# Power.net
KiCad netlist of a schematic drawn in Altium Designer
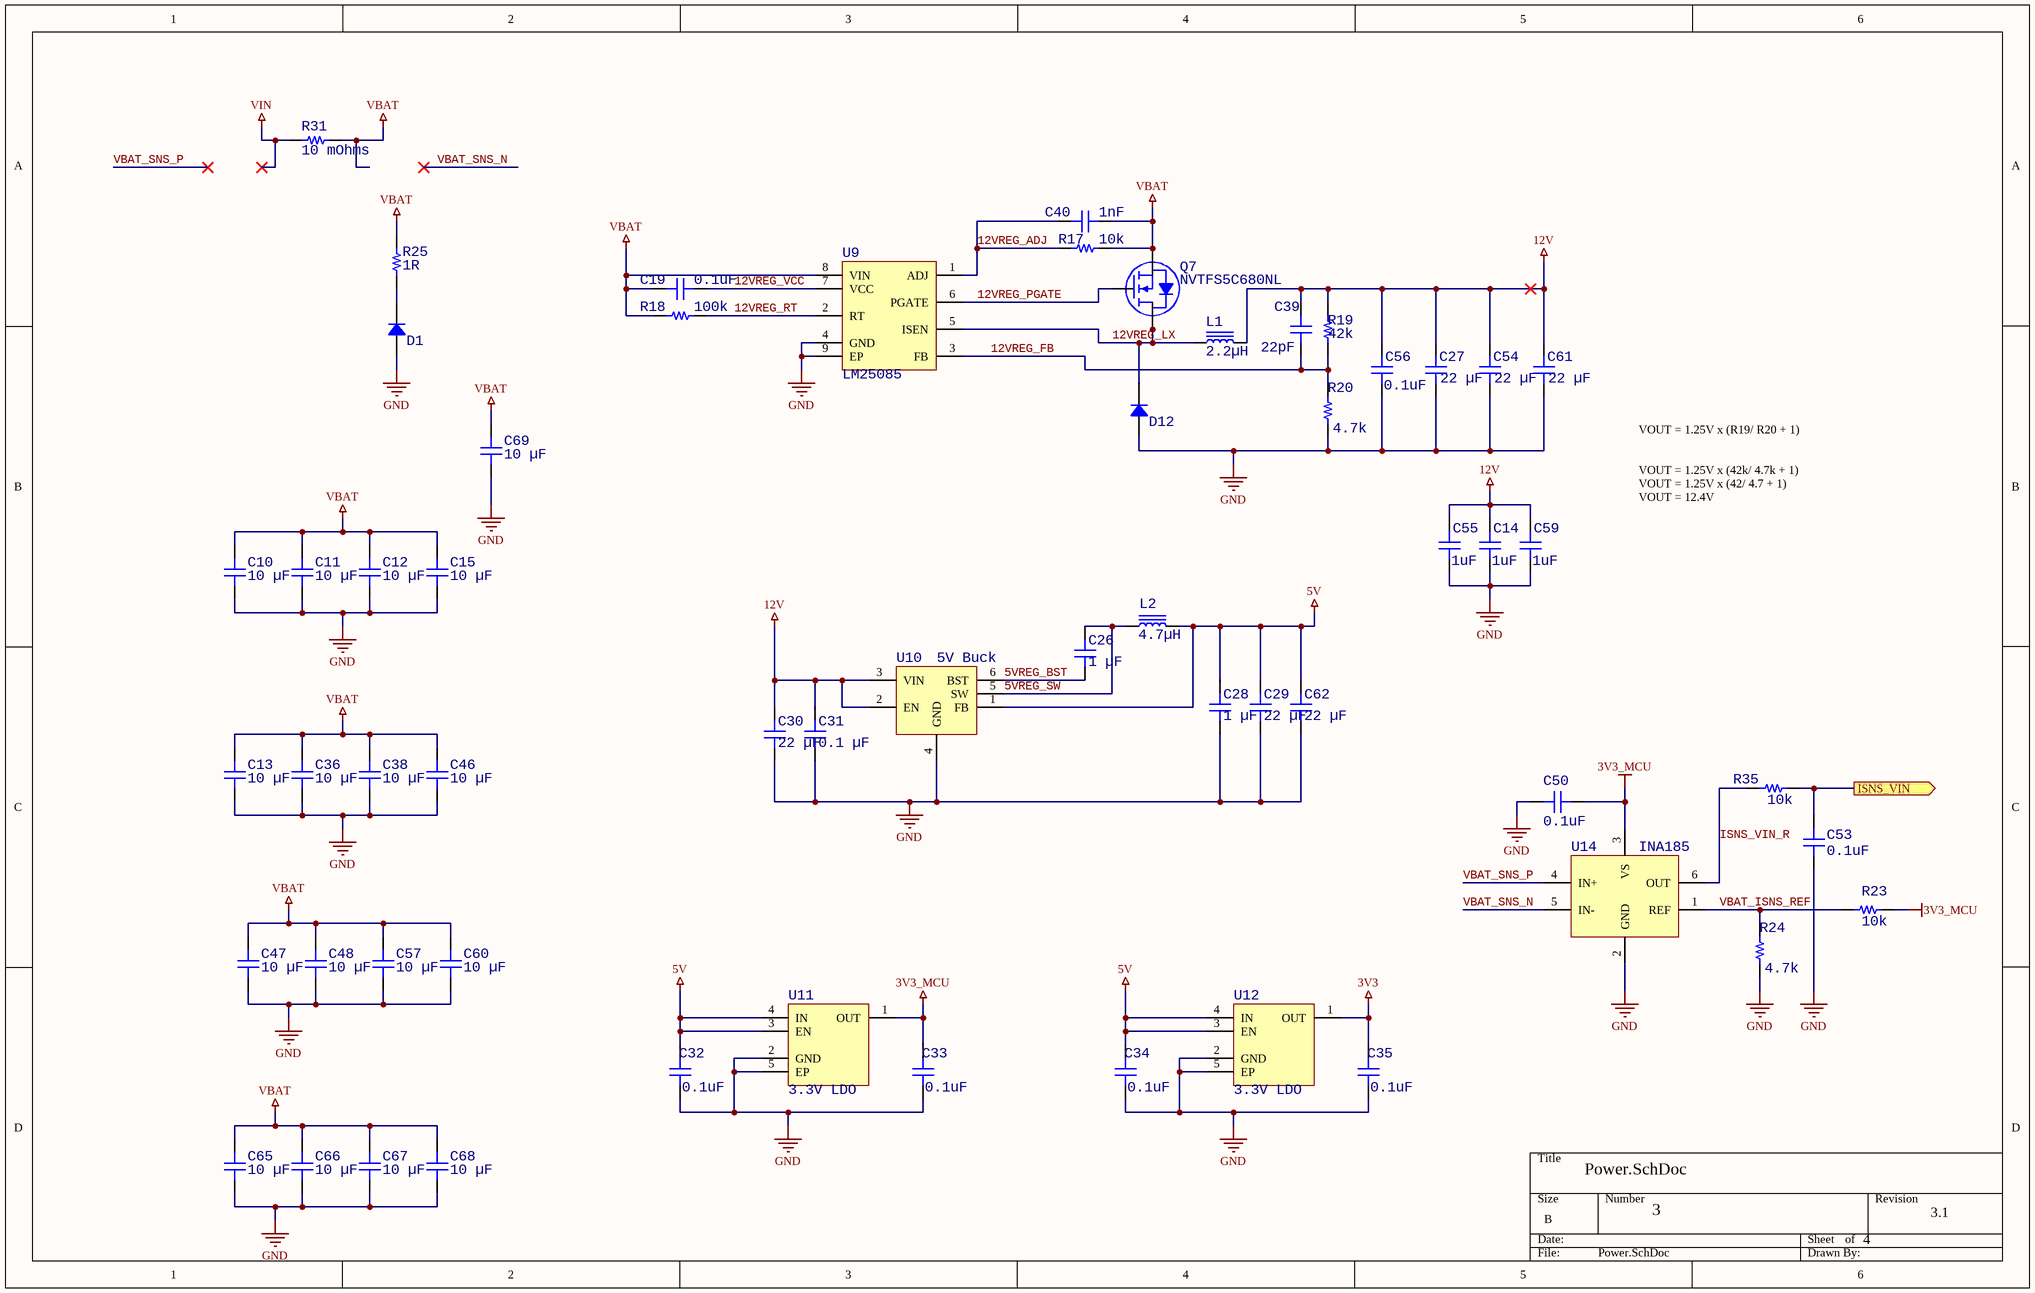
[diagram p0: Power.SchDoc]

(export (version "E")
  (design (tool "Eeschema 10.0.6"))
  (components
    (comp (ref "C10")
      (value "10 µF")
      (footprint "CAP 1206_3216 - 0.8MM")
      (description "CAP CER 10UF 25V X6S 1206")
      (fields
        (field (name "PART NUMBER") "CL31X106KAHNNNE")
        (field (name "MANUFACTURER") "Samsung Electro-Mechanics")
      )
      (libsource (lib "Celestial Altium Library - altium_library") (part "Capacitor"))
    )
    (comp (ref "C11")
      (value "10 µF")
      (footprint "CAP 1206_3216 - 0.8MM")
      (description "CAP CER 10UF 25V X6S 1206")
      (fields
        (field (name "PART NUMBER") "CL31X106KAHNNNE")
        (field (name "MANUFACTURER") "Samsung Electro-Mechanics")
      )
      (libsource (lib "Celestial Altium Library - altium_library") (part "Capacitor"))
    )
    (comp (ref "C12")
      (value "10 µF")
      (footprint "CAP 1206_3216 - 0.8MM")
      (description "CAP CER 10UF 25V X6S 1206")
      (fields
        (field (name "PART NUMBER") "CL31X106KAHNNNE")
        (field (name "MANUFACTURER") "Samsung Electro-Mechanics")
      )
      (libsource (lib "Celestial Altium Library - altium_library") (part "Capacitor"))
    )
    (comp (ref "C13")
      (value "10 µF")
      (footprint "CAP 1206_3216 - 0.8MM")
      (description "CAP CER 10UF 25V X6S 1206")
      (fields
        (field (name "PART NUMBER") "CL31X106KAHNNNE")
        (field (name "MANUFACTURER") "Samsung Electro-Mechanics")
      )
      (libsource (lib "Celestial Altium Library - altium_library") (part "Capacitor"))
    )
    (comp (ref "C14")
      (value "1uF")
      (footprint "CAP_0402")
      (description "CAP CER 402")
      (libsource (lib "IC") (part "CAP_0402"))
    )
    (comp (ref "C15")
      (value "10 µF")
      (footprint "CAP 1206_3216 - 0.8MM")
      (description "CAP CER 10UF 25V X6S 1206")
      (fields
        (field (name "PART NUMBER") "CL31X106KAHNNNE")
        (field (name "MANUFACTURER") "Samsung Electro-Mechanics")
      )
      (libsource (lib "Celestial Altium Library - altium_library") (part "Capacitor"))
    )
    (comp (ref "C19")
      (value "0.1uF")
      (footprint "CAP_0402")
      (description "CAP CER 402")
      (libsource (lib "IC") (part "CAP_0402"))
    )
    (comp (ref "C26")
      (value "1 µF")
      (footprint "CAP 0402_1005")
      (description "CAP CER 0.1UF 16V X7R 0402")
      (fields (field (name "PART NUMBER") "C0402C104K4RACAUTO") (field (name "MANUFACTURER") "KEMET"))
      (libsource (lib "Celestial Altium Library - altium_library") (part "Capacitor"))
    )
    (comp (ref "C27")
      (value "22 µF")
      (footprint "CAP 0805_2012")
      (description "CAP CER 22UF 16V X6S 0805")
      (fields (field (name "PART NUMBER") "KGM21AS61C226MU") (field (name "MANUFACTURER") "KYOCERA AVX"))
      (libsource (lib "Celestial Altium Library - altium_library") (part "Capacitor"))
    )
    (comp (ref "C28")
      (value "1 µF")
      (footprint "CAP 0402_1005")
      (description "CAP CER 0.1UF 16V X7R 0402")
      (fields (field (name "PART NUMBER") "C0402C104K4RACAUTO") (field (name "MANUFACTURER") "KEMET"))
      (libsource (lib "Celestial Altium Library - altium_library") (part "Capacitor"))
    )
    (comp (ref "C29")
      (value "22 µF")
      (footprint "CAP 0603_1608")
      (description "CAP CER 47UF 6.3V X5R 0603")
      (fields
        (field (name "PART NUMBER") "C0603B476M007T")
        (field (name "MANUFACTURER") "Holy Stone Enterprise Co., Ltd.")
      )
      (libsource (lib "Celestial Altium Library - altium_library") (part "Capacitor"))
    )
    (comp (ref "C30")
      (value "22 µF")
      (footprint "CAP 0603_1608")
      (description "CAP CER 47UF 6.3V X5R 0603")
      (fields
        (field (name "PART NUMBER") "C0603B476M007T")
        (field (name "MANUFACTURER") "Holy Stone Enterprise Co., Ltd.")
      )
      (libsource (lib "Celestial Altium Library - altium_library") (part "Capacitor"))
    )
    (comp (ref "C31")
      (value "0.1 µF")
      (footprint "CAP 0402_1005")
      (description "CAP CER 0.1UF 16V X7R 0402")
      (fields (field (name "PART NUMBER") "C0402C104K4RACAUTO") (field (name "MANUFACTURER") "KEMET"))
      (libsource (lib "Celestial Altium Library - altium_library") (part "Capacitor"))
    )
    (comp (ref "C32")
      (value "0.1uF")
      (footprint "CAP_0402")
      (description "CAP CER 402")
      (libsource (lib "IC") (part "CAP_0402"))
    )
    (comp (ref "C33")
      (value "0.1uF")
      (footprint "CAP_0402")
      (description "CAP CER 402")
      (libsource (lib "IC") (part "CAP_0402"))
    )
    (comp (ref "C34")
      (value "0.1uF")
      (footprint "CAP_0402")
      (description "CAP CER 402")
      (libsource (lib "IC") (part "CAP_0402"))
    )
    (comp (ref "C35")
      (value "0.1uF")
      (footprint "CAP_0402")
      (description "CAP CER 402")
      (libsource (lib "IC") (part "CAP_0402"))
    )
    (comp (ref "C36")
      (value "10 µF")
      (footprint "CAP 1206_3216 - 0.8MM")
      (description "CAP CER 10UF 25V X6S 1206")
      (fields
        (field (name "PART NUMBER") "CL31X106KAHNNNE")
        (field (name "MANUFACTURER") "Samsung Electro-Mechanics")
      )
      (libsource (lib "Celestial Altium Library - altium_library") (part "Capacitor"))
    )
    (comp (ref "C38")
      (value "10 µF")
      (footprint "CAP 1206_3216 - 0.8MM")
      (description "CAP CER 10UF 25V X6S 1206")
      (fields
        (field (name "PART NUMBER") "CL31X106KAHNNNE")
        (field (name "MANUFACTURER") "Samsung Electro-Mechanics")
      )
      (libsource (lib "Celestial Altium Library - altium_library") (part "Capacitor"))
    )
    (comp (ref "C39")
      (value "22pF")
      (footprint "CAP_0402")
      (description "CAP CER 402")
      (libsource (lib "IC") (part "CAP_0402"))
    )
    (comp (ref "C40")
      (value "1nF")
      (footprint "CAP_0402")
      (description "CAP CER 402")
      (libsource (lib "IC") (part "CAP_0402"))
    )
    (comp (ref "C46")
      (value "10 µF")
      (footprint "CAP 1206_3216 - 0.8MM")
      (description "CAP CER 10UF 25V X6S 1206")
      (fields
        (field (name "PART NUMBER") "CL31X106KAHNNNE")
        (field (name "MANUFACTURER") "Samsung Electro-Mechanics")
      )
      (libsource (lib "Celestial Altium Library - altium_library") (part "Capacitor"))
    )
    (comp (ref "C47")
      (value "10 µF")
      (footprint "CAP 1206_3216 - 0.8MM")
      (description "CAP CER 10UF 25V X6S 1206")
      (fields
        (field (name "PART NUMBER") "CL31X106KAHNNNE")
        (field (name "MANUFACTURER") "Samsung Electro-Mechanics")
      )
      (libsource (lib "Celestial Altium Library - altium_library") (part "Capacitor"))
    )
    (comp (ref "C48")
      (value "10 µF")
      (footprint "CAP 1206_3216 - 0.8MM")
      (description "CAP CER 10UF 25V X6S 1206")
      (fields
        (field (name "PART NUMBER") "CL31X106KAHNNNE")
        (field (name "MANUFACTURER") "Samsung Electro-Mechanics")
      )
      (libsource (lib "Celestial Altium Library - altium_library") (part "Capacitor"))
    )
    (comp (ref "C50")
      (value "0.1uF")
      (footprint "CAP_0402")
      (description "CAP CER 402")
      (libsource (lib "IC") (part "CAP_0402"))
    )
    (comp (ref "C53")
      (value "0.1uF")
      (footprint "CAP_0402")
      (description "CAP CER 402")
      (libsource (lib "IC") (part "CAP_0402"))
    )
    (comp (ref "C54")
      (value "22 µF")
      (footprint "CAP 0805_2012")
      (description "CAP CER 22UF 16V X6S 0805")
      (fields (field (name "PART NUMBER") "KGM21AS61C226MU") (field (name "MANUFACTURER") "KYOCERA AVX"))
      (libsource (lib "Celestial Altium Library - altium_library") (part "Capacitor"))
    )
    (comp (ref "C55")
      (value "1uF")
      (footprint "CAP_0402")
      (description "CAP CER 402")
      (libsource (lib "IC") (part "CAP_0402"))
    )
    (comp (ref "C56")
      (value "0.1uF")
      (footprint "CAP_0402")
      (description "CAP CER 402")
      (libsource (lib "IC") (part "CAP_0402"))
    )
    (comp (ref "C57")
      (value "10 µF")
      (footprint "CAP 1206_3216 - 0.8MM")
      (description "CAP CER 10UF 25V X6S 1206")
      (fields
        (field (name "PART NUMBER") "CL31X106KAHNNNE")
        (field (name "MANUFACTURER") "Samsung Electro-Mechanics")
      )
      (libsource (lib "Celestial Altium Library - altium_library") (part "Capacitor"))
    )
    (comp (ref "C59")
      (value "1uF")
      (footprint "CAP_0402")
      (description "CAP CER 402")
      (libsource (lib "IC") (part "CAP_0402"))
    )
    (comp (ref "C60")
      (value "10 µF")
      (footprint "CAP 1206_3216 - 0.8MM")
      (description "CAP CER 10UF 25V X6S 1206")
      (fields
        (field (name "PART NUMBER") "CL31X106KAHNNNE")
        (field (name "MANUFACTURER") "Samsung Electro-Mechanics")
      )
      (libsource (lib "Celestial Altium Library - altium_library") (part "Capacitor"))
    )
    (comp (ref "C61")
      (value "22 µF")
      (footprint "CAP 0805_2012")
      (description "CAP CER 22UF 16V X6S 0805")
      (fields (field (name "PART NUMBER") "KGM21AS61C226MU") (field (name "MANUFACTURER") "KYOCERA AVX"))
      (libsource (lib "Celestial Altium Library - altium_library") (part "Capacitor"))
    )
    (comp (ref "C62")
      (value "22 µF")
      (footprint "CAP 0603_1608")
      (description "CAP CER 47UF 6.3V X5R 0603")
      (fields
        (field (name "PART NUMBER") "C0603B476M007T")
        (field (name "MANUFACTURER") "Holy Stone Enterprise Co., Ltd.")
      )
      (libsource (lib "Celestial Altium Library - altium_library") (part "Capacitor"))
    )
    (comp (ref "C65")
      (value "10 µF")
      (footprint "CAP 1206_3216 - 0.8MM")
      (description "CAP CER 10UF 25V X6S 1206")
      (fields
        (field (name "PART NUMBER") "CL31X106KAHNNNE")
        (field (name "MANUFACTURER") "Samsung Electro-Mechanics")
      )
      (libsource (lib "Celestial Altium Library - altium_library") (part "Capacitor"))
    )
    (comp (ref "C66")
      (value "10 µF")
      (footprint "CAP 1206_3216 - 0.8MM")
      (description "CAP CER 10UF 25V X6S 1206")
      (fields
        (field (name "PART NUMBER") "CL31X106KAHNNNE")
        (field (name "MANUFACTURER") "Samsung Electro-Mechanics")
      )
      (libsource (lib "Celestial Altium Library - altium_library") (part "Capacitor"))
    )
    (comp (ref "C67")
      (value "10 µF")
      (footprint "CAP 1206_3216 - 0.8MM")
      (description "CAP CER 10UF 25V X6S 1206")
      (fields
        (field (name "PART NUMBER") "CL31X106KAHNNNE")
        (field (name "MANUFACTURER") "Samsung Electro-Mechanics")
      )
      (libsource (lib "Celestial Altium Library - altium_library") (part "Capacitor"))
    )
    (comp (ref "C68")
      (value "10 µF")
      (footprint "CAP 1206_3216 - 0.8MM")
      (description "CAP CER 10UF 25V X6S 1206")
      (fields
        (field (name "PART NUMBER") "CL31X106KAHNNNE")
        (field (name "MANUFACTURER") "Samsung Electro-Mechanics")
      )
      (libsource (lib "Celestial Altium Library - altium_library") (part "Capacitor"))
    )
    (comp (ref "C69")
      (value "10 µF")
      (footprint "CAP 1206_3216 - 0.8MM")
      (description "CAP CER 10UF 25V X6S 1206")
      (fields
        (field (name "PART NUMBER") "CL31X106KAHNNNE")
        (field (name "MANUFACTURER") "Samsung Electro-Mechanics")
      )
      (libsource (lib "Celestial Altium Library - altium_library") (part "Capacitor"))
    )
    (comp (ref "D1")
      (value "SE10FGHM3/H")
      (footprint "SMF DO-219AB")
      (description "DIODE GEN PURP 400V 1A DO219AB")
      (fields (field (name "MANUFACTURER") "Vishay Semiconductor Diodes Division"))
      (libsource (lib "Celestial Altium Library - altium_library") (part "Diode"))
    )
    (comp (ref "D12")
      (value "SE10FGHM3/H")
      (footprint "SMF DO-219AB")
      (description "DIODE GEN PURP 400V 1A DO219AB")
      (fields (field (name "MANUFACTURER") "Vishay Semiconductor Diodes Division"))
      (libsource (lib "Celestial Altium Library - altium_library") (part "Diode"))
    )
    (comp (ref "L1")
      (value "2.2µH")
      (footprint "IND 1008_2520")
      (description "FIXED IND 2.2UH 1.5A 90 MOHM SMD")
      (fields (field (name "PART NUMBER") "AIML-1008HC-2R2M-T") (field (name "MANUFACTURER") "Abracon LLC"))
      (libsource (lib "Celestial Altium Library - altium_library") (part "Inductor"))
    )
    (comp (ref "L2")
      (value "4.7µH")
      (footprint "IND 1008_2520")
      (description "FIXED IND 4.7UH 1A 110 MOHM SMD")
      (fields (field (name "PART NUMBER") "MLP2520S4R7ST0S1") (field (name "MANUFACTURER") "TDK Corporation"))
      (libsource (lib "Celestial Altium Library - altium_library") (part "Inductor"))
    )
    (comp (ref "Q7")
      (value "NVTFS5C680NL")
      (footprint "NVTFS015N04CTAG")
      (description "N-FET")
      (libsource (lib "IC") (part "NVTFS5C680NL"))
    )
    (comp (ref "R17")
      (value "10k")
      (footprint "RES_0402")
      (description "RES 0402")
      (libsource (lib "IC") (part "RES_0402"))
    )
    (comp (ref "R18")
      (value "100k")
      (footprint "RES_0402")
      (description "RES 0402")
      (libsource (lib "IC") (part "RES_0402"))
    )
    (comp (ref "R19")
      (value "42k")
      (footprint "RES_0402")
      (description "RES 0402")
      (libsource (lib "IC") (part "RES_0402"))
    )
    (comp (ref "R20")
      (value "4.7k")
      (footprint "RES_0402")
      (description "RES 0402")
      (libsource (lib "IC") (part "RES_0402"))
    )
    (comp (ref "R23")
      (value "10k")
      (footprint "RES_0402")
      (description "RES 0402")
      (libsource (lib "IC") (part "RES_0402"))
    )
    (comp (ref "R24")
      (value "4.7k")
      (footprint "RES_0402")
      (description "RES 0402")
      (libsource (lib "IC") (part "RES_0402"))
    )
    (comp (ref "R25")
      (value "1R")
      (footprint "RES 0603_1608")
      (description "1/16 WATTS PRECISION CHIP 1 KILO")
      (fields (field (name "PART NUMBER") "APC0603B1K00N") (field (name "MANUFACTURER") "Ohmite"))
      (libsource (lib "Celestial Altium Library - altium_library") (part "Resistor"))
    )
    (comp (ref "R31")
      (value "10 mOhms")
      (footprint "RES 1206_3216")
      (description "RES 0.039 OHM 1% 3/4W 1206")
      (fields (field (name "PART NUMBER") "KRL1632E-M-R039-F-T5") (field (name "MANUFACTURER") "Susumu"))
      (libsource (lib "Celestial Altium Library - altium_library") (part "Resistor"))
    )
    (comp (ref "R35")
      (value "10k")
      (footprint "RES_0402")
      (description "RES 0402")
      (libsource (lib "IC") (part "RES_0402"))
    )
    (comp (ref "U9")
      (value "LM25085")
      (footprint "8_WSON_3x3_0.5mm")
      (description "PFET Buck Controller")
      (libsource (lib "IC") (part "LM25085"))
    )
    (comp (ref "U10")
      (value "5V Buck")
      (footprint "TSOT-26-6 - 3.2mm")
      (description "5V fixed step down Buck")
      (libsource (lib "IC") (part "AP63205WU-7"))
    )
    (comp (ref "U11") (value "3.3V LDO") (footprint "XDFN-4") (libsource (lib "IC") (part "TLV74033PDQNR")))
    (comp (ref "U12") (value "3.3V LDO") (footprint "XDFN-4") (libsource (lib "IC") (part "TLV74033PDQNR")))
    (comp (ref "U14")
      (value "INA185")
      (footprint "TI SC70-6 DCK")
      (description "INA185A2")
      (libsource (lib "IC") (part "INA185"))
    )
  )
  (nets
    (net (code "1") (name "/5VREG_BST") (class "Default")
      (node (ref "C26") (pin "1") (pinfunction "1_1") (pintype "passive"))
      (node (ref "U10") (pin "6") (pinfunction "BST_6") (pintype "passive"))
    )
    (net (code "2") (name "/5VREG_SW") (class "Default")
      (node (ref "C26") (pin "2") (pinfunction "2_2") (pintype "passive"))
      (node (ref "L2") (pin "1") (pinfunction "1_1") (pintype "passive"))
      (node (ref "U10") (pin "5") (pinfunction "SW_5") (pintype "passive"))
    )
    (net (code "3") (name "/12VREG_ADJ") (class "Default")
      (node (ref "C40") (pin "1") (pinfunction "1_1") (pintype "passive"))
      (node (ref "R17") (pin "2") (pinfunction "2_2") (pintype "passive"))
      (node (ref "U9") (pin "1") (pinfunction "ADJ_1") (pintype "passive"))
    )
    (net (code "4") (name "/12VREG_FB") (class "Default")
      (node (ref "C39") (pin "1") (pinfunction "1_1") (pintype "passive"))
      (node (ref "R19") (pin "2") (pinfunction "2_2") (pintype "passive"))
      (node (ref "R20") (pin "1") (pinfunction "1_1") (pintype "passive"))
      (node (ref "U9") (pin "3") (pinfunction "FB_3") (pintype "passive"))
    )
    (net (code "5") (name "/12VREG_LX") (class "Default")
      (node (ref "D12") (pin "2") (pinfunction "2_2") (pintype "passive"))
      (node (ref "L1") (pin "1") (pinfunction "1_1") (pintype "passive"))
      (node (ref "Q7") (pin "5") (pinfunction "D_5") (pintype "passive"))
      (node (ref "Q7") (pin "6") (pinfunction "D_6") (pintype "passive"))
      (node (ref "Q7") (pin "7") (pinfunction "D_7") (pintype "passive"))
      (node (ref "Q7") (pin "8") (pinfunction "D_8") (pintype "passive"))
      (node (ref "U9") (pin "5") (pinfunction "ISEN_5") (pintype "passive"))
    )
    (net (code "6") (name "/12VREG_PGATE") (class "Default")
      (node (ref "Q7") (pin "4") (pinfunction "G_4") (pintype "passive"))
      (node (ref "U9") (pin "6") (pinfunction "PGATE_6") (pintype "passive"))
    )
    (net (code "7") (name "/12VREG_RT") (class "Default")
      (node (ref "R18") (pin "1") (pinfunction "1_1") (pintype "passive"))
      (node (ref "U9") (pin "2") (pinfunction "RT_2") (pintype "passive"))
    )
    (net (code "8") (name "/12VREG_VCC") (class "Default")
      (node (ref "C19") (pin "2") (pinfunction "2_2") (pintype "passive"))
      (node (ref "U9") (pin "7") (pinfunction "VCC_7") (pintype "passive"))
    )
    (net (code "9") (name "/ISNS_VIN") (class "Default")
      (node (ref "C53") (pin "1") (pinfunction "1_1") (pintype "passive"))
      (node (ref "R35") (pin "1") (pinfunction "1_1") (pintype "passive"))
    )
    (net (code "10") (name "/ISNS_VIN_R") (class "Default")
      (node (ref "R35") (pin "2") (pinfunction "2_2") (pintype "passive"))
      (node (ref "U14") (pin "6") (pinfunction "OUT_6") (pintype "passive"))
    )
    (net (code "11") (name "/VBAT_ISNS_REF") (class "Default")
      (node (ref "R23") (pin "2") (pinfunction "2_2") (pintype "passive"))
      (node (ref "R24") (pin "1") (pinfunction "1_1") (pintype "passive"))
      (node (ref "U14") (pin "1") (pinfunction "REF_1") (pintype "passive"))
    )
    (net (code "12") (name "/VBAT_SNS_N") (class "Default")
      (node (ref "U14") (pin "5") (pinfunction "IN-_5") (pintype "passive"))
    )
    (net (code "13") (name "/VBAT_SNS_P") (class "Default")
      (node (ref "U14") (pin "4") (pinfunction "IN+_4") (pintype "passive"))
    )
    (net (code "14") (name "3V3") (class "Default")
      (node (ref "C35") (pin "2") (pinfunction "2_2") (pintype "passive"))
      (node (ref "U12") (pin "1") (pinfunction "OUT_1") (pintype "passive"))
    )
    (net (code "15") (name "3V3_MCU") (class "Default")
      (node (ref "C33") (pin "2") (pinfunction "2_2") (pintype "passive"))
      (node (ref "C50") (pin "1") (pinfunction "1_1") (pintype "passive"))
      (node (ref "R23") (pin "1") (pinfunction "1_1") (pintype "passive"))
      (node (ref "U11") (pin "1") (pinfunction "OUT_1") (pintype "passive"))
      (node (ref "U14") (pin "3") (pinfunction "VS_3") (pintype "passive"))
    )
    (net (code "16") (name "5V") (class "Default")
      (node (ref "C28") (pin "2") (pinfunction "2_2") (pintype "passive"))
      (node (ref "C29") (pin "2") (pinfunction "2_2") (pintype "passive"))
      (node (ref "C32") (pin "2") (pinfunction "2_2") (pintype "passive"))
      (node (ref "C34") (pin "2") (pinfunction "2_2") (pintype "passive"))
      (node (ref "C62") (pin "2") (pinfunction "2_2") (pintype "passive"))
      (node (ref "L2") (pin "2") (pinfunction "2_2") (pintype "passive"))
      (node (ref "U10") (pin "1") (pinfunction "FB_1") (pintype "passive"))
      (node (ref "U11") (pin "3") (pinfunction "EN_3") (pintype "passive"))
      (node (ref "U11") (pin "4") (pinfunction "IN_4") (pintype "passive"))
      (node (ref "U12") (pin "3") (pinfunction "EN_3") (pintype "passive"))
      (node (ref "U12") (pin "4") (pinfunction "IN_4") (pintype "passive"))
    )
    (net (code "17") (name "12V") (class "Default")
      (node (ref "C14") (pin "2") (pinfunction "2_2") (pintype "passive"))
      (node (ref "C27") (pin "2") (pinfunction "2_2") (pintype "passive"))
      (node (ref "C30") (pin "2") (pinfunction "2_2") (pintype "passive"))
      (node (ref "C31") (pin "2") (pinfunction "2_2") (pintype "passive"))
      (node (ref "C39") (pin "2") (pinfunction "2_2") (pintype "passive"))
      (node (ref "C54") (pin "2") (pinfunction "2_2") (pintype "passive"))
      (node (ref "C55") (pin "2") (pinfunction "2_2") (pintype "passive"))
      (node (ref "C56") (pin "2") (pinfunction "2_2") (pintype "passive"))
      (node (ref "C59") (pin "2") (pinfunction "2_2") (pintype "passive"))
      (node (ref "C61") (pin "2") (pinfunction "2_2") (pintype "passive"))
      (node (ref "L1") (pin "2") (pinfunction "2_2") (pintype "passive"))
      (node (ref "R19") (pin "1") (pinfunction "1_1") (pintype "passive"))
      (node (ref "U10") (pin "2") (pinfunction "EN_2") (pintype "passive"))
      (node (ref "U10") (pin "3") (pinfunction "VIN_3") (pintype "passive"))
    )
    (net (code "18") (name "GND") (class "Default")
      (node (ref "C10") (pin "1") (pinfunction "1_1") (pintype "passive"))
      (node (ref "C11") (pin "1") (pinfunction "1_1") (pintype "passive"))
      (node (ref "C12") (pin "1") (pinfunction "1_1") (pintype "passive"))
      (node (ref "C13") (pin "1") (pinfunction "1_1") (pintype "passive"))
      (node (ref "C14") (pin "1") (pinfunction "1_1") (pintype "passive"))
      (node (ref "C15") (pin "1") (pinfunction "1_1") (pintype "passive"))
      (node (ref "C27") (pin "1") (pinfunction "1_1") (pintype "passive"))
      (node (ref "C28") (pin "1") (pinfunction "1_1") (pintype "passive"))
      (node (ref "C29") (pin "1") (pinfunction "1_1") (pintype "passive"))
      (node (ref "C30") (pin "1") (pinfunction "1_1") (pintype "passive"))
      (node (ref "C31") (pin "1") (pinfunction "1_1") (pintype "passive"))
      (node (ref "C32") (pin "1") (pinfunction "1_1") (pintype "passive"))
      (node (ref "C33") (pin "1") (pinfunction "1_1") (pintype "passive"))
      (node (ref "C34") (pin "1") (pinfunction "1_1") (pintype "passive"))
      (node (ref "C35") (pin "1") (pinfunction "1_1") (pintype "passive"))
      (node (ref "C36") (pin "1") (pinfunction "1_1") (pintype "passive"))
      (node (ref "C38") (pin "1") (pinfunction "1_1") (pintype "passive"))
      (node (ref "C46") (pin "1") (pinfunction "1_1") (pintype "passive"))
      (node (ref "C47") (pin "1") (pinfunction "1_1") (pintype "passive"))
      (node (ref "C48") (pin "1") (pinfunction "1_1") (pintype "passive"))
      (node (ref "C50") (pin "2") (pinfunction "2_2") (pintype "passive"))
      (node (ref "C53") (pin "2") (pinfunction "2_2") (pintype "passive"))
      (node (ref "C54") (pin "1") (pinfunction "1_1") (pintype "passive"))
      (node (ref "C55") (pin "1") (pinfunction "1_1") (pintype "passive"))
      (node (ref "C56") (pin "1") (pinfunction "1_1") (pintype "passive"))
      (node (ref "C57") (pin "1") (pinfunction "1_1") (pintype "passive"))
      (node (ref "C59") (pin "1") (pinfunction "1_1") (pintype "passive"))
      (node (ref "C60") (pin "1") (pinfunction "1_1") (pintype "passive"))
      (node (ref "C61") (pin "1") (pinfunction "1_1") (pintype "passive"))
      (node (ref "C62") (pin "1") (pinfunction "1_1") (pintype "passive"))
      (node (ref "C65") (pin "1") (pinfunction "1_1") (pintype "passive"))
      (node (ref "C66") (pin "1") (pinfunction "1_1") (pintype "passive"))
      (node (ref "C67") (pin "1") (pinfunction "1_1") (pintype "passive"))
      (node (ref "C68") (pin "1") (pinfunction "1_1") (pintype "passive"))
      (node (ref "C69") (pin "1") (pinfunction "1_1") (pintype "passive"))
      (node (ref "D1") (pin "1") (pinfunction "1_1") (pintype "passive"))
      (node (ref "D12") (pin "1") (pinfunction "1_1") (pintype "passive"))
      (node (ref "R20") (pin "2") (pinfunction "2_2") (pintype "passive"))
      (node (ref "R24") (pin "2") (pinfunction "2_2") (pintype "passive"))
      (node (ref "U10") (pin "4") (pinfunction "GND_4") (pintype "passive"))
      (node (ref "U11") (pin "2") (pinfunction "GND_2") (pintype "passive"))
      (node (ref "U11") (pin "5") (pinfunction "EP_5") (pintype "passive"))
      (node (ref "U12") (pin "2") (pinfunction "GND_2") (pintype "passive"))
      (node (ref "U12") (pin "5") (pinfunction "EP_5") (pintype "passive"))
      (node (ref "U14") (pin "2") (pinfunction "GND_2") (pintype "passive"))
      (node (ref "U9") (pin "4") (pinfunction "GND_4") (pintype "passive"))
      (node (ref "U9") (pin "9") (pinfunction "EP_9") (pintype "passive"))
    )
    (net (code "19") (name "Net-(D1-Pad2)") (class "Default")
      (node (ref "D1") (pin "2") (pinfunction "2_2") (pintype "passive"))
      (node (ref "R25") (pin "1") (pinfunction "1_1") (pintype "passive"))
    )
    (net (code "20") (name "VBAT") (class "Default")
      (node (ref "C10") (pin "2") (pinfunction "2_2") (pintype "passive"))
      (node (ref "C11") (pin "2") (pinfunction "2_2") (pintype "passive"))
      (node (ref "C12") (pin "2") (pinfunction "2_2") (pintype "passive"))
      (node (ref "C13") (pin "2") (pinfunction "2_2") (pintype "passive"))
      (node (ref "C15") (pin "2") (pinfunction "2_2") (pintype "passive"))
      (node (ref "C19") (pin "1") (pinfunction "1_1") (pintype "passive"))
      (node (ref "C36") (pin "2") (pinfunction "2_2") (pintype "passive"))
      (node (ref "C38") (pin "2") (pinfunction "2_2") (pintype "passive"))
      (node (ref "C40") (pin "2") (pinfunction "2_2") (pintype "passive"))
      (node (ref "C46") (pin "2") (pinfunction "2_2") (pintype "passive"))
      (node (ref "C47") (pin "2") (pinfunction "2_2") (pintype "passive"))
      (node (ref "C48") (pin "2") (pinfunction "2_2") (pintype "passive"))
      (node (ref "C57") (pin "2") (pinfunction "2_2") (pintype "passive"))
      (node (ref "C60") (pin "2") (pinfunction "2_2") (pintype "passive"))
      (node (ref "C65") (pin "2") (pinfunction "2_2") (pintype "passive"))
      (node (ref "C66") (pin "2") (pinfunction "2_2") (pintype "passive"))
      (node (ref "C67") (pin "2") (pinfunction "2_2") (pintype "passive"))
      (node (ref "C68") (pin "2") (pinfunction "2_2") (pintype "passive"))
      (node (ref "C69") (pin "2") (pinfunction "2_2") (pintype "passive"))
      (node (ref "Q7") (pin "1") (pinfunction "S_1") (pintype "passive"))
      (node (ref "Q7") (pin "2") (pinfunction "S_2") (pintype "passive"))
      (node (ref "Q7") (pin "3") (pinfunction "S_3") (pintype "passive"))
      (node (ref "R17") (pin "1") (pinfunction "1_1") (pintype "passive"))
      (node (ref "R18") (pin "2") (pinfunction "2_2") (pintype "passive"))
      (node (ref "R25") (pin "2") (pinfunction "2_2") (pintype "passive"))
      (node (ref "R31") (pin "2") (pinfunction "2_2") (pintype "passive"))
      (node (ref "U9") (pin "8") (pinfunction "VIN_8") (pintype "passive"))
    )
    (net (code "21") (name "VIN") (class "Default")
      (node (ref "R31") (pin "1") (pinfunction "1_1") (pintype "passive"))
    )
  )
)
